# Overview.net
KiCad netlist of a schematic drawn in Altium Designer
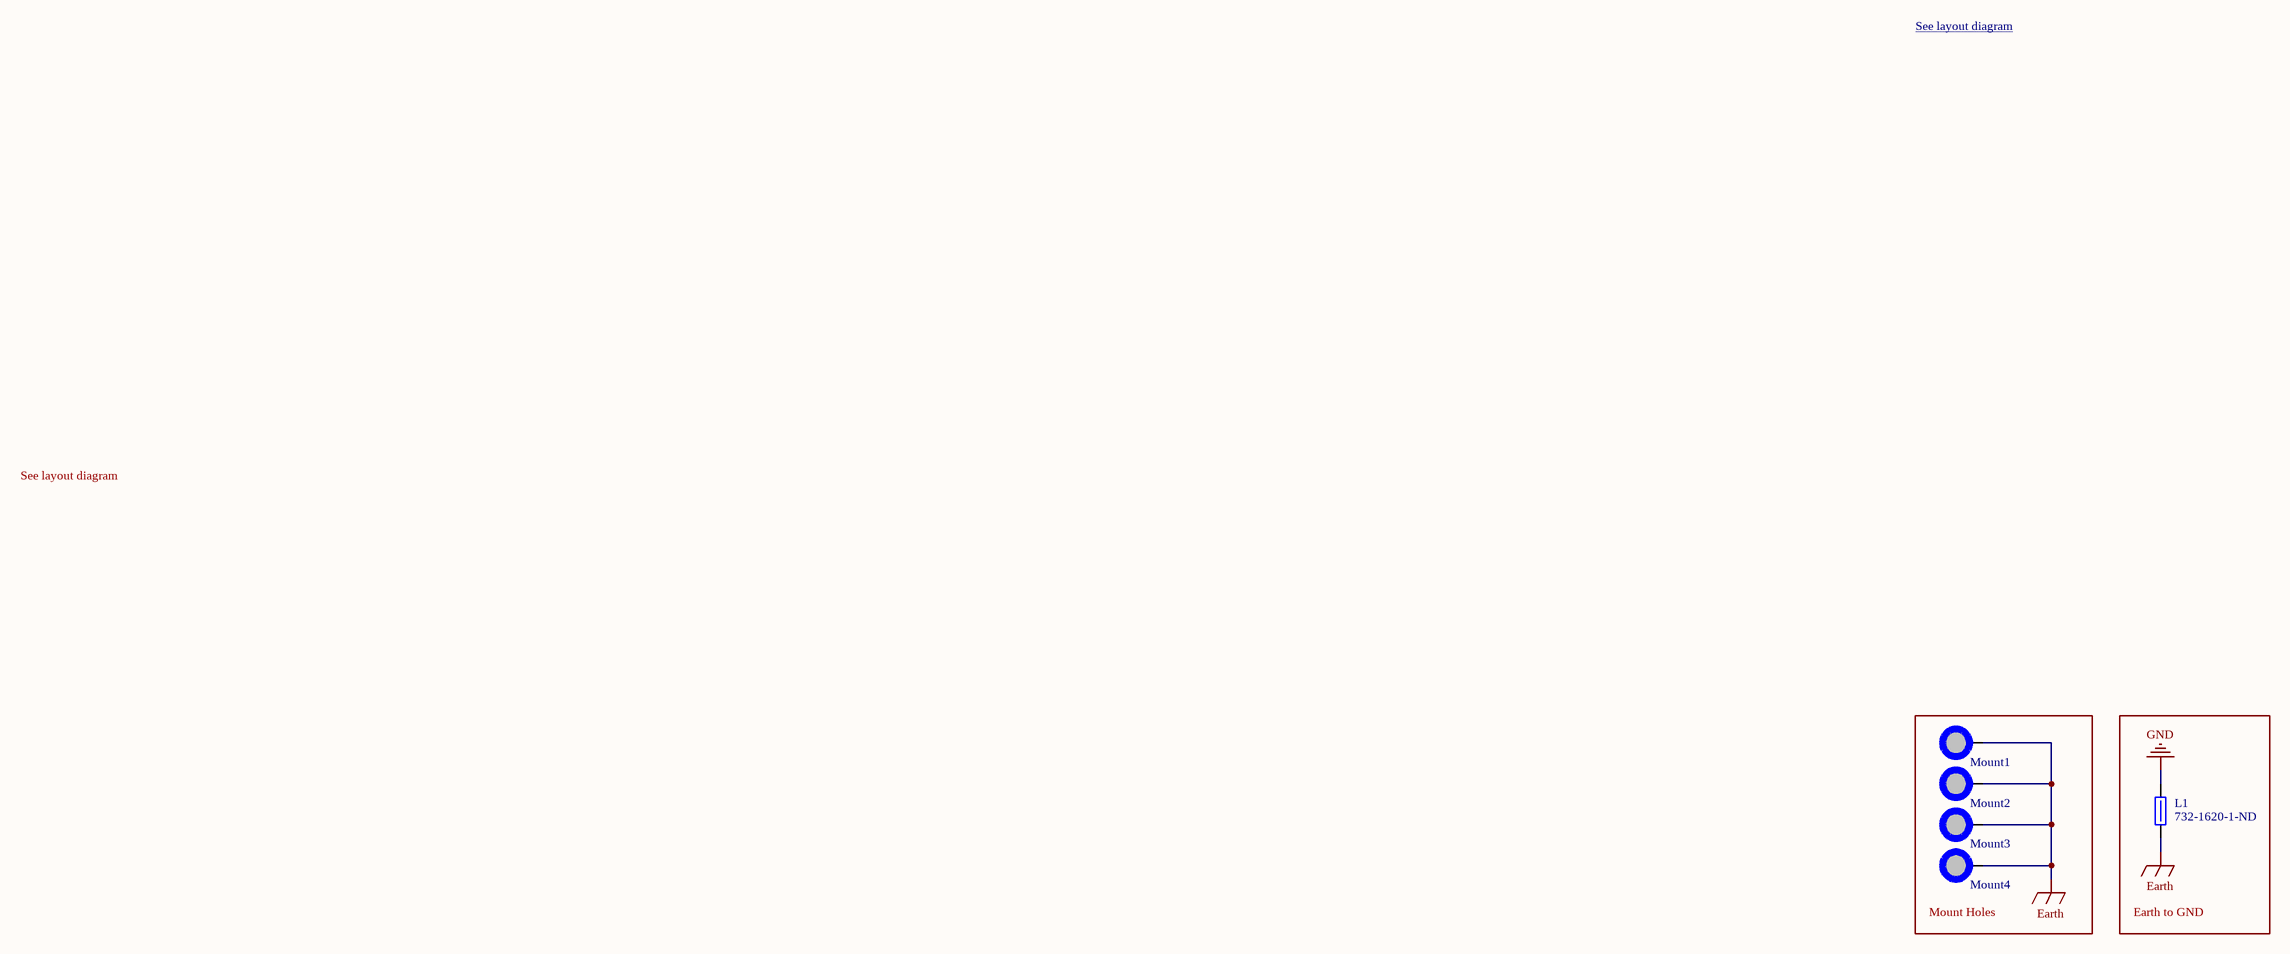
[diagram p0: Overview.SchDoc]

(export (version "E")
  (design (tool "Eeschema 10.0.6"))
  (components
    (comp (ref "L1")
      (value "742792040")
      (footprint "[Ferrite] SMD Bead 0805 (2)")
      (fields (field (name "SUPPLIER PART NUMBER 1") "732-1620-1-ND"))
      (libsource (lib "RADM Components") (part "[Ferrite] SMD Ferrite Bead (2)"))
    )
    (comp (ref "Mount1")
      (value "M3 Mount Hole")
      (footprint "[Mount] M3 Mount Hole")
      (description "Place at least 4.5mm from board edge. Plated.")
      (libsource (lib "RADM Connectors") (part "[Mount] M3 Mount Hole"))
    )
    (comp (ref "Mount2")
      (value "M3 Mount Hole")
      (footprint "[Mount] M3 Mount Hole")
      (description "Place at least 4.5mm from board edge. Plated.")
      (libsource (lib "RADM Connectors") (part "[Mount] M3 Mount Hole"))
    )
    (comp (ref "Mount3")
      (value "M3 Mount Hole")
      (footprint "[Mount] M3 Mount Hole")
      (description "Place at least 4.5mm from board edge. Plated.")
      (libsource (lib "RADM Connectors") (part "[Mount] M3 Mount Hole"))
    )
    (comp (ref "Mount4")
      (value "M3 Mount Hole")
      (footprint "[Mount] M3 Mount Hole")
      (description "Place at least 4.5mm from board edge. Plated.")
      (libsource (lib "RADM Connectors") (part "[Mount] M3 Mount Hole"))
    )
  )
  (nets
    (net (code "1") (name "Earth") (class "Default")
      (node (ref "L1") (pin "1") (pinfunction "1_1") (pintype "passive"))
      (node (ref "Mount1") (pin "1") (pintype "power_in"))
      (node (ref "Mount2") (pin "1") (pintype "power_in"))
      (node (ref "Mount3") (pin "1") (pintype "power_in"))
      (node (ref "Mount4") (pin "1") (pintype "power_in"))
    )
    (net (code "2") (name "GND") (class "Default")
      (node (ref "L1") (pin "2") (pinfunction "2_2") (pintype "passive"))
    )
  )
)
